# KickerManager.net
KiCad netlist of a schematic drawn in Altium Designer
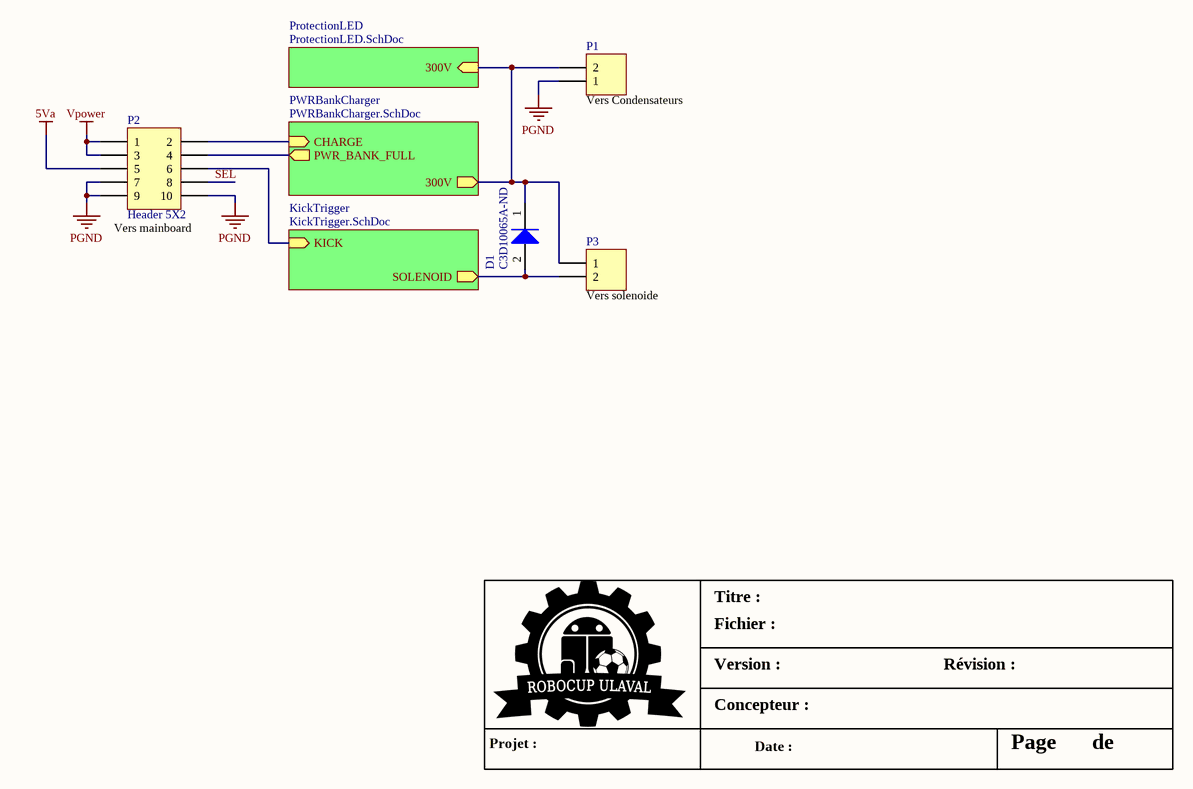
[diagram p0: KickerManager.SchDoc]

(export (version "E")
  (design (tool "Eeschema 10.0.6"))
  (components
    (comp (ref "D1")
      (value "Diode 1N4007")
      (footprint "TO-220-2")
      (description "DIODE SCHOTTKY 650V 10A TO220-2")
      (fields
        (field (name "MANUFACTURER") "Cree/Wolfspeed")
        (field (name "MANUFACTURER PART NUMBER") "C3D10065A")
        (field (name "SUPPLIER PART NUMBER 1") "C3D10065A-ND")
      )
      (libsource (lib "gamma_gestionkicker") (part "Diode 1N4007"))
    )
    (comp (ref "P1")
      (value "Header 2")
      (footprint "0.156mil header")
      (description "Header, 2-Pin, 0.156mil")
      (libsource (lib "") (part "Header 2pin 0.156_1"))
    )
    (comp (ref "P2")
      (value "Header 5X2")
      (footprint "HDR2X5")
      (description "Header, 5-Pin, Dual row")
      (fields (field (name "PUBLISHER") "Altium Limited"))
      (libsource (lib "Miscellaneous Connectors") (part "Header 5X2"))
    )
    (comp (ref "P3")
      (value "Header 2")
      (footprint "0.156mil header")
      (description "Header, 2-Pin, 0.156mil")
      (libsource (lib "gamma_gestionkicker") (part "Header 2pin 0.156"))
    )
  )
  (nets
    (net (code "1") (name "/300V") (class "Default")
      (node (ref "D1") (pin "1") (pinfunction "K_1") (pintype "passive"))
      (node (ref "P1") (pin "2") (pinfunction "2_2") (pintype "passive"))
      (node (ref "P3") (pin "1") (pinfunction "1_1") (pintype "passive"))
    )
    (net (code "2") (name "/CHARGE") (class "Default")
      (node (ref "P2") (pin "2") (pinfunction "2_2") (pintype "passive"))
    )
    (net (code "3") (name "/KICK") (class "Default")
      (node (ref "P2") (pin "6") (pinfunction "6_6") (pintype "passive"))
    )
    (net (code "4") (name "/PWR_BANK_FULL") (class "Default")
      (node (ref "P2") (pin "4") (pinfunction "4_4") (pintype "passive"))
    )
    (net (code "5") (name "/SEL") (class "Default")
      (node (ref "P2") (pin "8") (pinfunction "8_8") (pintype "passive"))
    )
    (net (code "6") (name "/SOLENOID") (class "Default")
      (node (ref "D1") (pin "2") (pinfunction "A_2") (pintype "passive"))
      (node (ref "P3") (pin "2") (pinfunction "2_2") (pintype "passive"))
    )
    (net (code "7") (name "5Va") (class "Default")
      (node (ref "P2") (pin "5") (pinfunction "5_5") (pintype "passive"))
    )
    (net (code "8") (name "PGND") (class "Default")
      (node (ref "P1") (pin "1") (pinfunction "1_1") (pintype "passive"))
      (node (ref "P2") (pin "10") (pinfunction "10_10") (pintype "passive"))
      (node (ref "P2") (pin "7") (pinfunction "7_7") (pintype "passive"))
      (node (ref "P2") (pin "9") (pinfunction "9_9") (pintype "passive"))
    )
    (net (code "9") (name "Vpower") (class "Default")
      (node (ref "P2") (pin "1") (pinfunction "1_1") (pintype "passive"))
      (node (ref "P2") (pin "3") (pinfunction "3_3") (pintype "passive"))
    )
  )
)
